# 3V3_Supply.net
KiCad netlist of a schematic drawn in Altium Designer
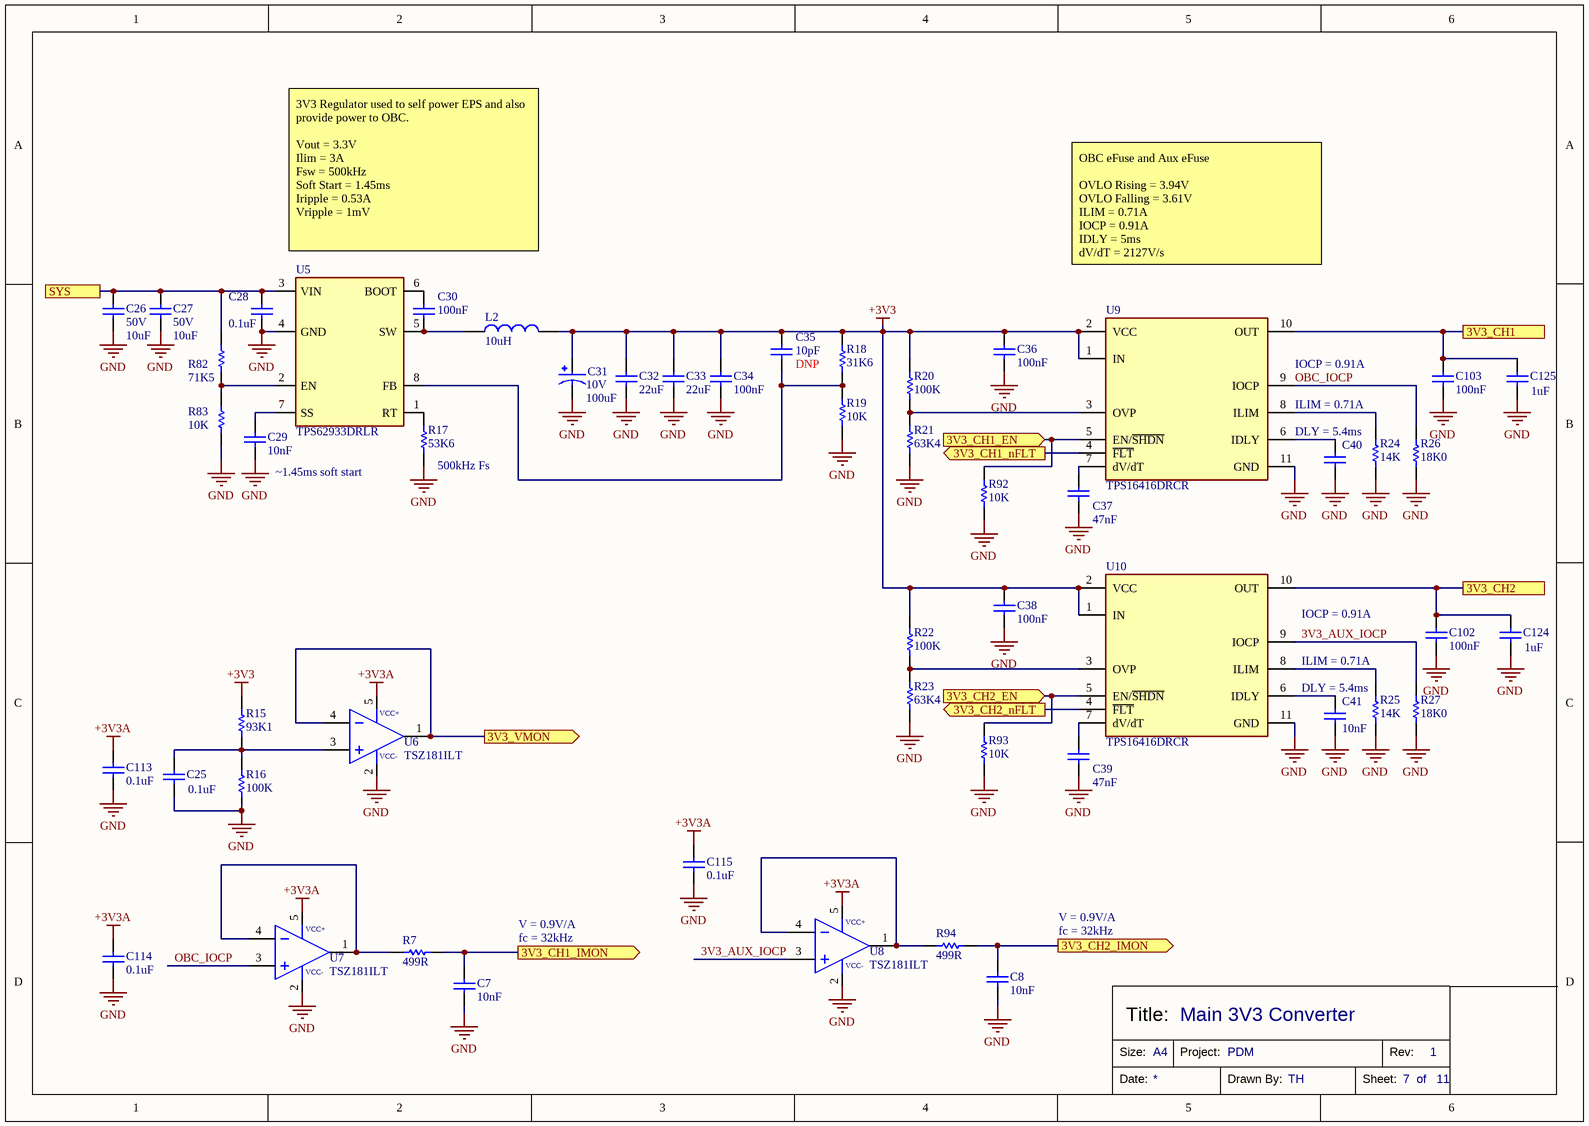
[diagram p0: 3V3_Supply.SchDoc]

(export (version "E")
  (design (tool "Eeschema 10.0.6"))
  (components
    (comp (ref "C7")
      (value "CL21B103KBANNNC")
      (footprint "CAPC0805X060")
      (description "10nF ±10% 50V Ceramic Capacitor X7R 0805 (2012 Metric)")
      (fields
        (field (name "DISTRIBUTOR PART NUMBER") "1276-1015-1-ND")
        (field (name "TOLERANCE") "10%")
        (field (name "CAPACITANCE") "10nF")
      )
      (libsource (lib "Ahristi_Library") (part "CL21B103KBANNNC"))
    )
    (comp (ref "C8")
      (value "CL21B103KBANNNC")
      (footprint "CAPC0805X060")
      (description "10nF ±10% 50V Ceramic Capacitor X7R 0805 (2012 Metric)")
      (fields
        (field (name "DISTRIBUTOR PART NUMBER") "1276-1015-1-ND")
        (field (name "TOLERANCE") "10%")
        (field (name "CAPACITANCE") "10nF")
      )
      (libsource (lib "Ahristi_Library") (part "CL21B103KBANNNC"))
    )
    (comp (ref "C25")
      (value "CL21B104KACNNNC")
      (footprint "CAPC0805X060")
      (description "0.1uF ±10% 25V Ceramic Capacitor X7R 0805 (2012 Metric)")
      (fields
        (field (name "DISTRIBUTOR PART NUMBER") "1276-1099-1-ND")
        (field (name "TOLERANCE") "10%")
        (field (name "CAPACITANCE") "0.1uF")
      )
      (libsource (lib "Ahristi_Library") (part "CL21B104KACNNNC"))
    )
    (comp (ref "C26")
      (value "CL32B106KBJNNNE")
      (footprint "CAPC1210X090")
      (description "10 µF ±10% 50V Ceramic Capacitor X7R 1210 (3225 Metric)")
      (fields
        (field (name "DISTRIBUTOR PART NUMBER") "1276-3387-1-ND")
        (field (name "TOLERANCE") "10%")
        (field (name "VOLTAGE RATING") "50V")
        (field (name "CAPACITANCE") "10uF")
      )
      (libsource (lib "Ahristi_Library") (part "CL32B106KBJNNNE"))
    )
    (comp (ref "C27")
      (value "CL32B106KBJNNNE")
      (footprint "CAPC1210X090")
      (description "10 µF ±10% 50V Ceramic Capacitor X7R 1210 (3225 Metric)")
      (fields
        (field (name "DISTRIBUTOR PART NUMBER") "1276-3387-1-ND")
        (field (name "TOLERANCE") "10%")
        (field (name "VOLTAGE RATING") "50V")
        (field (name "CAPACITANCE") "10uF")
      )
      (libsource (lib "Ahristi_Library") (part "CL32B106KBJNNNE"))
    )
    (comp (ref "C28")
      (value "CL05B104KB5NNNC")
      (footprint "CAPC0402X020")
      (description "0.1 µF ±10% 50V Ceramic Capacitor X7R 0402 (1005 Metric)")
      (fields
        (field (name "TOLERANCE") "10%")
        (field (name "DISTRIBUTOR PART NUMBER") "1276-CL05B104KB5NNNCCT-ND")
        (field (name "CAPACITANCE") "0.1uF")
      )
      (libsource (lib "Ahristi_Library") (part "CL05B104KB5NNNC"))
    )
    (comp (ref "C29")
      (value "CL21B103KBANNNC")
      (footprint "CAPC0805X060")
      (description "10nF ±10% 50V Ceramic Capacitor X7R 0805 (2012 Metric)")
      (fields
        (field (name "DISTRIBUTOR PART NUMBER") "1276-1015-1-ND")
        (field (name "TOLERANCE") "10%")
        (field (name "CAPACITANCE") "10nF")
      )
      (libsource (lib "Ahristi_Library") (part "CL21B103KBANNNC"))
    )
    (comp (ref "C30")
      (value "C0603C104K5RACTU")
      (footprint "CAPC0603X040")
      (description "0.1 µF ±10% 50V Ceramic Capacitor X7R 0603 (1608 Metric)")
      (fields
        (field (name "DISTRIBUTOR PART NUMBER") "399-C0603C104K5RACTUCT-ND")
        (field (name "TOLERANCE") "10%")
        (field (name "CAPACITANCE") "100nF")
      )
      (libsource (lib "Ahristi_Library") (part "C0603C104K5RACTU"))
    )
    (comp (ref "C31")
      (value "TPSC107K010R0100")
      (footprint "2312 Tantalum")
      (description "100 µF Molded Tantalum Capacitors 10 V 2312 (6032 Metric) 100mOhm")
      (fields
        (field (name "DISTRIBUTOR PART NUMBER") "478-1765-1-ND")
        (field (name "VOLTAGE RATING") "10V")
        (field (name "CAPACITANCE") "100uF")
      )
      (libsource (lib "Ahristi_Library") (part "TPSC107K010R0100"))
    )
    (comp (ref "C32")
      (value "GRM21BZ71A226ME15L")
      (footprint "CAPC0805X060")
      (description "22 µF ±20% 10V Ceramic Capacitor X7R 0805 (2012 Metric)")
      (fields
        (field (name "DISTRIBUTOR PART NUMBER") "490-GRM21BZ71A226ME15LCT-ND")
        (field (name "TOLERANCE") "10%")
        (field (name "CAPACITANCE") "22uF")
      )
      (libsource (lib "Ahristi_Library") (part "GRM21BZ71A226ME15L"))
    )
    (comp (ref "C33")
      (value "GRM21BZ71A226ME15L")
      (footprint "CAPC0805X060")
      (description "22 µF ±20% 10V Ceramic Capacitor X7R 0805 (2012 Metric)")
      (fields
        (field (name "DISTRIBUTOR PART NUMBER") "490-GRM21BZ71A226ME15LCT-ND")
        (field (name "TOLERANCE") "10%")
        (field (name "CAPACITANCE") "22uF")
      )
      (libsource (lib "Ahristi_Library") (part "GRM21BZ71A226ME15L"))
    )
    (comp (ref "C34")
      (value "C0603C104K5RACTU")
      (footprint "CAPC0603X040")
      (description "0.1 µF ±10% 50V Ceramic Capacitor X7R 0603 (1608 Metric)")
      (fields
        (field (name "DISTRIBUTOR PART NUMBER") "399-C0603C104K5RACTUCT-ND")
        (field (name "TOLERANCE") "10%")
        (field (name "CAPACITANCE") "100nF")
      )
      (libsource (lib "Ahristi_Library") (part "C0603C104K5RACTU"))
    )
    (comp (ref "C35")
      (value "C0603C104K5RACTU")
      (footprint "CAPC0603X040")
      (description "10 pF ±5% 50V Ceramic Capacitor C0G, NP0 0603 (1608 Metric)")
      (fields
        (field (name "PART NUMBER") "C0603C100J5GACTU")
        (field (name "DISTRIBUTOR PART NUMBER") "399-C0603C100J5GACTUCT-ND")
        (field (name "CAPACITANCE") "10pF")
      )
      (libsource (lib "Ahristi_Library") (part "C0603C100J5GACTU"))
    )
    (comp (ref "C36")
      (value "C0603C104K5RACTU")
      (footprint "CAPC0603X040")
      (description "0.1 µF ±10% 50V Ceramic Capacitor X7R 0603 (1608 Metric)")
      (fields
        (field (name "DISTRIBUTOR PART NUMBER") "399-C0603C104K5RACTUCT-ND")
        (field (name "TOLERANCE") "10%")
        (field (name "CAPACITANCE") "100nF")
      )
      (libsource (lib "Ahristi_Library") (part "C0603C104K5RACTU"))
    )
    (comp (ref "C37")
      (value "CL21B473KBCNNNC")
      (footprint "CAPC0805X060")
      (description "0.047 µF ±10% 50V Ceramic Capacitor X7R 0805 (2012 Metric)")
      (fields
        (field (name "DISTRIBUTOR PART NUMBER") "1276-1250-1-ND")
        (field (name "TOLERANCE") "10%")
        (field (name "CAPACITANCE") "47nF")
      )
      (libsource (lib "Ahristi_Library") (part "CL21B473KBCNNNC"))
    )
    (comp (ref "C38")
      (value "C0603C104K5RACTU")
      (footprint "CAPC0603X040")
      (description "0.1 µF ±10% 50V Ceramic Capacitor X7R 0603 (1608 Metric)")
      (fields
        (field (name "DISTRIBUTOR PART NUMBER") "399-C0603C104K5RACTUCT-ND")
        (field (name "TOLERANCE") "10%")
        (field (name "CAPACITANCE") "100nF")
      )
      (libsource (lib "Ahristi_Library") (part "C0603C104K5RACTU"))
    )
    (comp (ref "C39")
      (value "CL21B473KBCNNNC")
      (footprint "CAPC0805X060")
      (description "0.047 µF ±10% 50V Ceramic Capacitor X7R 0805 (2012 Metric)")
      (fields
        (field (name "DISTRIBUTOR PART NUMBER") "1276-1250-1-ND")
        (field (name "TOLERANCE") "10%")
        (field (name "CAPACITANCE") "47nF")
      )
      (libsource (lib "Ahristi_Library") (part "CL21B473KBCNNNC"))
    )
    (comp (ref "C40")
      (value "CL21B103KBANNNC")
      (footprint "CAPC0805X060")
      (description "10nF ±10% 50V Ceramic Capacitor X7R 0805 (2012 Metric)")
      (fields (field (name "DISTRIBUTOR PART NUMBER") "1276-1015-1-ND") (field (name "TOLERANCE") "10%"))
      (libsource (lib "Ahristi_Library") (part "CL21B103KBANNNC"))
    )
    (comp (ref "C41")
      (value "CL21B103KBANNNC")
      (footprint "CAPC0805X060")
      (description "10nF ±10% 50V Ceramic Capacitor X7R 0805 (2012 Metric)")
      (fields
        (field (name "DISTRIBUTOR PART NUMBER") "1276-1015-1-ND")
        (field (name "TOLERANCE") "10%")
        (field (name "CAPACITANCE") "10nF")
      )
      (libsource (lib "Ahristi_Library") (part "CL21B103KBANNNC"))
    )
    (comp (ref "C102")
      (value "C0603C104K5RACTU")
      (footprint "CAPC0603X040")
      (description "0.1 µF ±10% 50V Ceramic Capacitor X7R 0603 (1608 Metric)")
      (fields
        (field (name "DISTRIBUTOR PART NUMBER") "399-C0603C104K5RACTUCT-ND")
        (field (name "TOLERANCE") "10%")
        (field (name "CAPACITANCE") "100nF")
      )
      (libsource (lib "Ahristi_Library") (part "C0603C104K5RACTU"))
    )
    (comp (ref "C103")
      (value "C0603C104K5RACTU")
      (footprint "CAPC0603X040")
      (description "0.1 µF ±10% 50V Ceramic Capacitor X7R 0603 (1608 Metric)")
      (fields
        (field (name "DISTRIBUTOR PART NUMBER") "399-C0603C104K5RACTUCT-ND")
        (field (name "TOLERANCE") "10%")
        (field (name "CAPACITANCE") "100nF")
      )
      (libsource (lib "Ahristi_Library") (part "C0603C104K5RACTU"))
    )
    (comp (ref "C113")
      (value "C0603C104K5RACTU")
      (footprint "CAPC0603X040")
      (description "0.1 µF ±10% 50V Ceramic Capacitor X7R 0603 (1608 Metric)")
      (fields
        (field (name "DISTRIBUTOR PART NUMBER") "399-C0603C104K5RACTUCT-ND")
        (field (name "TOLERANCE") "10%")
        (field (name "CAPACITANCE") "0.1uF")
      )
      (libsource (lib "Ahristi_Library") (part "C0603C104K5RACTU"))
    )
    (comp (ref "C114")
      (value "C0603C104K5RACTU")
      (footprint "CAPC0603X040")
      (description "0.1 µF ±10% 50V Ceramic Capacitor X7R 0603 (1608 Metric)")
      (fields
        (field (name "DISTRIBUTOR PART NUMBER") "399-C0603C104K5RACTUCT-ND")
        (field (name "TOLERANCE") "10%")
        (field (name "CAPACITANCE") "0.1uF")
      )
      (libsource (lib "Ahristi_Library") (part "C0603C104K5RACTU"))
    )
    (comp (ref "C115")
      (value "C0603C104K5RACTU")
      (footprint "CAPC0603X040")
      (description "0.1 µF ±10% 50V Ceramic Capacitor X7R 0603 (1608 Metric)")
      (fields
        (field (name "DISTRIBUTOR PART NUMBER") "399-C0603C104K5RACTUCT-ND")
        (field (name "TOLERANCE") "10%")
        (field (name "CAPACITANCE") "0.1uF")
      )
      (libsource (lib "Ahristi_Library") (part "C0603C104K5RACTU"))
    )
    (comp (ref "C124")
      (value "CL21B105KAFNNNE")
      (footprint "CAPC0805X060")
      (description "1uF ±10% 25V Ceramic Capacitor X7R 0805 (2012 Metric)")
      (fields
        (field (name "DISTRIBUTOR PART NUMBER") "1276-1066-1-ND")
        (field (name "TOLERANCE") "10%")
        (field (name "CAPACITANCE") "1uF")
      )
      (libsource (lib "Ahristi_Library") (part "CL21B105KAFNNNE"))
    )
    (comp (ref "C125")
      (value "CL21B105KAFNNNE")
      (footprint "CAPC0805X060")
      (description "1uF ±10% 25V Ceramic Capacitor X7R 0805 (2012 Metric)")
      (fields
        (field (name "DISTRIBUTOR PART NUMBER") "1276-1066-1-ND")
        (field (name "TOLERANCE") "10%")
        (field (name "CAPACITANCE") "1uF")
      )
      (libsource (lib "Ahristi_Library") (part "CL21B105KAFNNNE"))
    )
    (comp (ref "L2")
      (value "1274AS-H-100M=P3")
      (footprint "1274AS-H-100M=P3")
      (description "Inductor 10 µH , 4.4 A 30.4mOhm Max Shielded Drum Core")
      (fields (field (name "DISTRIBUTOR PART NUMBER") "490-10846-1-ND") (field (name "INDUCTANCE") "10uH"))
      (libsource (lib "Ahristi_Library") (part "1274AS-H-100M=P3"))
    )
    (comp (ref "R7")
      (value "RMCF0805FT499R")
      (footprint "RESC0805")
      (description "499 Ohms ±1% 0.125W, 1/8W Chip Resistor 0805 (2012 Metric) Automotive AEC-Q200 Thick Film")
      (fields
        (field (name "TOLERANCE") "1%")
        (field (name "DISTRIBUTOR PART NUMBER") "RMCF0805FT499RCT-ND")
        (field (name "RESISTANCE") "499R")
      )
      (libsource (lib "Ahristi_Library") (part "RMCF0805FT499R"))
    )
    (comp (ref "R15")
      (value "RMCF0603FT93K1")
      (footprint "RESC0603")
      (description "93.1 kOhms ±1% 0.1W, 1/10W Chip Resistor 0603 (1608 Metric) Automotive AEC-Q200 Thick Film")
      (fields
        (field (name "TOLERANCE") "1%")
        (field (name "DISTRIBUTOR PART NUMBER") "RMCF0603FT93K1CT-ND")
        (field (name "RESISTANCE") "93K1")
      )
      (libsource (lib "Ahristi_Library") (part "RMCF0603FT93K1"))
    )
    (comp (ref "R16")
      (value "RMCF0603FT100K")
      (footprint "RESC0603")
      (description "100 kOhms ±1% 0.1W, 1/10W Chip Resistor 0603 (1608 Metric) Automotive AEC-Q200 Thick Film")
      (fields
        (field (name "TOLERANCE") "1%")
        (field (name "DISTRIBUTOR PART NUMBER") "RMCF0603FT100KCT-ND")
        (field (name "RESISTANCE") "100K")
      )
      (libsource (lib "Ahristi_Library") (part "RMCF0603FT100K"))
    )
    (comp (ref "R17")
      (value "RMCF0805FT53K6")
      (footprint "RESC0805")
      (description "53.6 kOhms ±1% 0.125W, 1/8W Chip Resistor 0805 (2012 Metric) Automotive AEC-Q200 Thick Film")
      (fields
        (field (name "TOLERANCE") "1%")
        (field (name "DISTRIBUTOR PART NUMBER") "RMCF0805FT53K6CT-ND")
        (field (name "RESISTANCE") "53K6")
      )
      (libsource (lib "Ahristi_Library") (part "RMCF0805FT53K6"))
    )
    (comp (ref "R18")
      (value "RMCF0603FT31K6")
      (footprint "RESC0603")
      (description "31.6 kOhms ±1% 0.1W, 1/10W Chip Resistor 0603 (1608 Metric) Automotive AEC-Q200 Thick Film")
      (fields
        (field (name "TOLERANCE") "1%")
        (field (name "DISTRIBUTOR PART NUMBER") "RMCF0603FT31K6CT-ND")
        (field (name "RESISTANCE") "31K6")
      )
      (libsource (lib "Ahristi_Library") (part "RMCF0603FT31K6"))
    )
    (comp (ref "R19")
      (value "RMCF0603FT10K0")
      (footprint "RESC0603")
      (description "10 kOhms ±1% 0.1W, 1/10W Chip Resistor 0603 (1608 Metric) Automotive AEC-Q200 Thick Film")
      (fields
        (field (name "TOLERANCE") "1%")
        (field (name "DISTRIBUTOR PART NUMBER") "RMCF0603FT10K0CT-ND")
        (field (name "RESISTANCE") "10K")
      )
      (libsource (lib "Ahristi_Library") (part "RMCF0603FT10K0"))
    )
    (comp (ref "R20")
      (value "RMCF0805FG100K")
      (footprint "RESC0805")
      (description "100 kOhms ±1% 0.125W, 1/8W Chip Resistor 0805 (2012 Metric) Automotive AEC-Q200 Thick Film")
      (fields
        (field (name "TOLERANCE") "1%")
        (field (name "DISTRIBUTOR PART NUMBER") "RMCF0805FG100KCT-ND")
        (field (name "RESISTANCE") "100K")
      )
      (libsource (lib "Ahristi_Library") (part "RMCF0805FG100K"))
    )
    (comp (ref "R21")
      (value "RMCF0805FT63K4")
      (footprint "RESC0805")
      (description "63.4 kOhms ±1% 0.125W, 1/8W Chip Resistor 0805 (2012 Metric) Automotive AEC-Q200 Thick Film")
      (fields
        (field (name "TOLERANCE") "1%")
        (field (name "DISTRIBUTOR PART NUMBER") "RMCF0805FT63K4CT-ND")
        (field (name "RESISTANCE") "63K4")
      )
      (libsource (lib "Ahristi_Library") (part "RMCF0805FT63K4"))
    )
    (comp (ref "R22")
      (value "RMCF0805FG100K")
      (footprint "RESC0805")
      (description "100 kOhms ±1% 0.125W, 1/8W Chip Resistor 0805 (2012 Metric) Automotive AEC-Q200 Thick Film")
      (fields
        (field (name "TOLERANCE") "1%")
        (field (name "DISTRIBUTOR PART NUMBER") "RMCF0805FG100KCT-ND")
        (field (name "RESISTANCE") "100K")
      )
      (libsource (lib "Ahristi_Library") (part "RMCF0805FG100K"))
    )
    (comp (ref "R23")
      (value "RMCF0805FT63K4")
      (footprint "RESC0805")
      (description "63.4 kOhms ±1% 0.125W, 1/8W Chip Resistor 0805 (2012 Metric) Automotive AEC-Q200 Thick Film")
      (fields
        (field (name "TOLERANCE") "1%")
        (field (name "DISTRIBUTOR PART NUMBER") "RMCF0805FT63K4CT-ND")
        (field (name "RESISTANCE") "63K4")
      )
      (libsource (lib "Ahristi_Library") (part "RMCF0805FT63K4"))
    )
    (comp (ref "R24")
      (value "RMCF0805FT14K0")
      (footprint "RESC0805")
      (description "14 kOhms ±1% 0.125W, 1/8W Chip Resistor 0805 (2012 Metric) Automotive AEC-Q200 Thick Film")
      (fields
        (field (name "TOLERANCE") "1%")
        (field (name "DISTRIBUTOR PART NUMBER") "RMCF0805FT14K0CT-ND")
        (field (name "RESISTANCE") "14K")
      )
      (libsource (lib "Ahristi_Library") (part "RMCF0805FT14K0"))
    )
    (comp (ref "R25")
      (value "RMCF0805FT14K0")
      (footprint "RESC0805")
      (description "14 kOhms ±1% 0.125W, 1/8W Chip Resistor 0805 (2012 Metric) Automotive AEC-Q200 Thick Film")
      (fields
        (field (name "TOLERANCE") "1%")
        (field (name "DISTRIBUTOR PART NUMBER") "RMCF0805FT14K0CT-ND")
        (field (name "RESISTANCE") "14K")
      )
      (libsource (lib "Ahristi_Library") (part "RMCF0805FT14K0"))
    )
    (comp (ref "R26")
      (value "RMCF0805FT18K0")
      (footprint "RESC0805")
      (description "18 kOhms ±1% 0.125W, 1/8W Chip Resistor 0805 (2012 Metric) Automotive AEC-Q200 Thick Film")
      (fields
        (field (name "TOLERANCE") "1%")
        (field (name "DISTRIBUTOR PART NUMBER") "RMCF0805FT18K0CT-ND")
        (field (name "RESISTANCE") "18K0")
      )
      (libsource (lib "Ahristi_Library") (part "RMCF0805FT18K0"))
    )
    (comp (ref "R27")
      (value "RMCF0805FT18K0")
      (footprint "RESC0805")
      (description "18 kOhms ±1% 0.125W, 1/8W Chip Resistor 0805 (2012 Metric) Automotive AEC-Q200 Thick Film")
      (fields
        (field (name "TOLERANCE") "1%")
        (field (name "DISTRIBUTOR PART NUMBER") "RMCF0805FT18K0CT-ND")
        (field (name "RESISTANCE") "18K0")
      )
      (libsource (lib "Ahristi_Library") (part "RMCF0805FT18K0"))
    )
    (comp (ref "R82")
      (value "RMCF0805FT71K5")
      (footprint "RESC0805")
      (description "71.5 kOhms ±1% 0.125W, 1/8W Chip Resistor 0805 (2012 Metric) Automotive AEC-Q200 Thick Film")
      (fields
        (field (name "TOLERANCE") "1%")
        (field (name "DISTRIBUTOR PART NUMBER") "RMCF0805FT71K5CT-ND")
        (field (name "RESISTANCE") "71K5")
      )
      (libsource (lib "Ahristi_Library") (part "RMCF0805FT71K5"))
    )
    (comp (ref "R83")
      (value "RMCF0603FT10K0")
      (footprint "RESC0603")
      (description "10 kOhms ±1% 0.1W, 1/10W Chip Resistor 0603 (1608 Metric) Automotive AEC-Q200 Thick Film")
      (fields
        (field (name "TOLERANCE") "1%")
        (field (name "DISTRIBUTOR PART NUMBER") "RMCF0603FT10K0CT-ND")
        (field (name "RESISTANCE") "10K")
      )
      (libsource (lib "Ahristi_Library") (part "RMCF0603FT10K0"))
    )
    (comp (ref "R92")
      (value "RMCF0805FT10K0")
      (footprint "RESC0805")
      (description "10 kOhms ±1% 0.125W, 1/8W Chip Resistor 0805 (2012 Metric) Automotive AEC-Q200 Thick Film")
      (fields
        (field (name "TOLERANCE") "1%")
        (field (name "DISTRIBUTOR PART NUMBER") "RMCF0805FT10K0CT-ND")
        (field (name "RESISTANCE") "10K")
      )
      (libsource (lib "Ahristi_Library") (part "RMCF0805FT10K0"))
    )
    (comp (ref "R93")
      (value "RMCF0805FT10K0")
      (footprint "RESC0805")
      (description "10 kOhms ±1% 0.125W, 1/8W Chip Resistor 0805 (2012 Metric) Automotive AEC-Q200 Thick Film")
      (fields
        (field (name "TOLERANCE") "1%")
        (field (name "DISTRIBUTOR PART NUMBER") "RMCF0805FT10K0CT-ND")
        (field (name "RESISTANCE") "10K")
      )
      (libsource (lib "Ahristi_Library") (part "RMCF0805FT10K0"))
    )
    (comp (ref "R94")
      (value "RMCF0805FT499R")
      (footprint "RESC0805")
      (description "499 Ohms ±1% 0.125W, 1/8W Chip Resistor 0805 (2012 Metric) Automotive AEC-Q200 Thick Film")
      (fields
        (field (name "TOLERANCE") "1%")
        (field (name "DISTRIBUTOR PART NUMBER") "RMCF0805FT499RCT-ND")
        (field (name "RESISTANCE") "499R")
      )
      (libsource (lib "Ahristi_Library") (part "RMCF0805FT499R"))
    )
    (comp (ref "U5")
      (value "TPS62933DRLR")
      (footprint "SOT-583")
      (description "Buck Switching Regulator IC Positive Adjustable 0.8V 1 Output 3A SOT-583")
      (fields (field (name "DISTRIBUTOR PART NUMBER") "296-TPS62933DRLRCT-ND"))
      (libsource (lib "Ahristi_Library") (part "TPS62933DRLR"))
    )
    (comp (ref "U6")
      (value "TSZ181ILT")
      (footprint "SOT23-5 IC")
      (description "Operational Amplifier, General Purpose, 2.2V~5.5V")
      (fields (field (name "DISTRIBUTOR PART NUMBER") "497-18084-1-ND"))
      (libsource (lib "Ahristi_Library") (part "TSZ181ILT"))
    )
    (comp (ref "U7")
      (value "TSZ181ILT")
      (footprint "SOT23-5 IC")
      (description "Operational Amplifier, General Purpose, 2.2V~5.5V")
      (fields (field (name "DISTRIBUTOR PART NUMBER") "497-18084-1-ND"))
      (libsource (lib "Ahristi_Library") (part "TSZ181ILT"))
    )
    (comp (ref "U8")
      (value "TSZ181ILT")
      (footprint "SOT23-5 IC")
      (description "Operational Amplifier, General Purpose, 2.2V~5.5V")
      (fields (field (name "DISTRIBUTOR PART NUMBER") "497-18084-1-ND"))
      (libsource (lib "Ahristi_Library") (part "TSZ181ILT"))
    )
    (comp (ref "U9")
      (value "TPS16410DRCR")
      (footprint "TPS1641")
      (description "2.7-V to 40-V 152-mΩ 1.8-A eFuse with output power limiting")
      (fields
        (field (name "DISTRIBUTOR PART NUMBER") "296-TPS16410DRCRCT-ND")
        (field (name "PART NUMBER") "TPS16416DRCR")
      )
      (libsource (lib "Ahristi_Library") (part "TPS16410DRCR"))
    )
    (comp (ref "U10")
      (value "TPS16410DRCR")
      (footprint "TPS1641")
      (description "2.7-V to 40-V 152-mΩ 1.8-A eFuse with output power limiting")
      (fields
        (field (name "DISTRIBUTOR PART NUMBER") "296-TPS16410DRCRCT-ND")
        (field (name "PART NUMBER") "TPS16416DRCR")
      )
      (libsource (lib "Ahristi_Library") (part "TPS16410DRCR"))
    )
  )
  (nets
    (net (code "1") (name "+3V3") (class "Default")
      (node (ref "C31") (pin "1") (pinfunction "1_1") (pintype "passive"))
      (node (ref "C32") (pin "2") (pinfunction "2_2") (pintype "passive"))
      (node (ref "C33") (pin "2") (pinfunction "2_2") (pintype "passive"))
      (node (ref "C34") (pin "2") (pinfunction "2_2") (pintype "passive"))
      (node (ref "C35") (pin "2") (pinfunction "2_2") (pintype "passive"))
      (node (ref "C36") (pin "2") (pinfunction "2_2") (pintype "passive"))
      (node (ref "C38") (pin "2") (pinfunction "2_2") (pintype "passive"))
      (node (ref "L2") (pin "2") (pinfunction "2_2") (pintype "passive"))
      (node (ref "R15") (pin "2") (pinfunction "2_2") (pintype "passive"))
      (node (ref "R18") (pin "2") (pinfunction "2_2") (pintype "passive"))
      (node (ref "R20") (pin "2") (pinfunction "2_2") (pintype "passive"))
      (node (ref "R22") (pin "2") (pinfunction "2_2") (pintype "passive"))
      (node (ref "U10") (pin "1") (pinfunction "IN_1") (pintype "passive"))
      (node (ref "U10") (pin "2") (pinfunction "VCC_2") (pintype "passive"))
      (node (ref "U9") (pin "1") (pinfunction "IN_1") (pintype "passive"))
      (node (ref "U9") (pin "2") (pinfunction "VCC_2") (pintype "passive"))
    )
    (net (code "2") (name "+3V3A") (class "Default")
      (node (ref "C113") (pin "2") (pinfunction "2_2") (pintype "passive"))
      (node (ref "C114") (pin "2") (pinfunction "2_2") (pintype "passive"))
      (node (ref "C115") (pin "2") (pinfunction "2_2") (pintype "passive"))
      (node (ref "U6") (pin "5") (pinfunction "VCC+_5") (pintype "power_in"))
      (node (ref "U7") (pin "5") (pinfunction "VCC+_5") (pintype "power_in"))
      (node (ref "U8") (pin "5") (pinfunction "VCC+_5") (pintype "power_in"))
    )
    (net (code "3") (name "/3V3_AUX_IOCP") (class "Default")
      (node (ref "R27") (pin "2") (pinfunction "2_2") (pintype "passive"))
      (node (ref "U10") (pin "9") (pinfunction "IOCP_9") (pintype "passive"))
      (node (ref "U8") (pin "3") (pinfunction "IN+_3") (pintype "passive"))
    )
    (net (code "4") (name "/3V3_CH1") (class "Default")
      (node (ref "C103") (pin "2") (pinfunction "2_2") (pintype "passive"))
      (node (ref "C125") (pin "2") (pinfunction "2_2") (pintype "passive"))
      (node (ref "U9") (pin "10") (pinfunction "OUT_10") (pintype "passive"))
    )
    (net (code "5") (name "/3V3_CH1_EN") (class "Default")
      (node (ref "R92") (pin "2") (pinfunction "2_2") (pintype "passive"))
      (node (ref "U9") (pin "5") (pinfunction "EN/~{SHDN}_5") (pintype "passive"))
    )
    (net (code "6") (name "/3V3_CH1_IMON") (class "Default")
      (node (ref "C7") (pin "2") (pinfunction "2_2") (pintype "passive"))
      (node (ref "R7") (pin "2") (pinfunction "2_2") (pintype "passive"))
    )
    (net (code "7") (name "/3V3_CH1_nFLT") (class "Default")
      (node (ref "U9") (pin "4") (pinfunction "~{FLT}_4") (pintype "passive"))
    )
    (net (code "8") (name "/3V3_CH2") (class "Default")
      (node (ref "C102") (pin "2") (pinfunction "2_2") (pintype "passive"))
      (node (ref "C124") (pin "2") (pinfunction "2_2") (pintype "passive"))
      (node (ref "U10") (pin "10") (pinfunction "OUT_10") (pintype "passive"))
    )
    (net (code "9") (name "/3V3_CH2_EN") (class "Default")
      (node (ref "R93") (pin "2") (pinfunction "2_2") (pintype "passive"))
      (node (ref "U10") (pin "5") (pinfunction "EN/~{SHDN}_5") (pintype "passive"))
    )
    (net (code "10") (name "/3V3_CH2_IMON") (class "Default")
      (node (ref "C8") (pin "2") (pinfunction "2_2") (pintype "passive"))
      (node (ref "R94") (pin "2") (pinfunction "2_2") (pintype "passive"))
    )
    (net (code "11") (name "/3V3_CH2_nFLT") (class "Default")
      (node (ref "U10") (pin "4") (pinfunction "~{FLT}_4") (pintype "passive"))
    )
    (net (code "12") (name "/3V3_VMON") (class "Default")
      (node (ref "U6") (pin "1") (pinfunction "OUT_1") (pintype "passive"))
      (node (ref "U6") (pin "4") (pinfunction "IN-_4") (pintype "passive"))
    )
    (net (code "13") (name "/OBC_IOCP") (class "Default")
      (node (ref "R26") (pin "2") (pinfunction "2_2") (pintype "passive"))
      (node (ref "U7") (pin "3") (pinfunction "IN+_3") (pintype "passive"))
      (node (ref "U9") (pin "9") (pinfunction "IOCP_9") (pintype "passive"))
    )
    (net (code "14") (name "/SYS") (class "Default")
      (node (ref "C26") (pin "2") (pinfunction "2_2") (pintype "passive"))
      (node (ref "C27") (pin "2") (pinfunction "2_2") (pintype "passive"))
      (node (ref "C28") (pin "2") (pinfunction "2_2") (pintype "passive"))
      (node (ref "R82") (pin "2") (pinfunction "2_2") (pintype "passive"))
      (node (ref "U5") (pin "3") (pinfunction "VIN_3") (pintype "passive"))
    )
    (net (code "15") (name "GND") (class "Default")
      (node (ref "C102") (pin "1") (pinfunction "1_1") (pintype "passive"))
      (node (ref "C103") (pin "1") (pinfunction "1_1") (pintype "passive"))
      (node (ref "C113") (pin "1") (pinfunction "1_1") (pintype "passive"))
      (node (ref "C114") (pin "1") (pinfunction "1_1") (pintype "passive"))
      (node (ref "C115") (pin "1") (pinfunction "1_1") (pintype "passive"))
      (node (ref "C124") (pin "1") (pinfunction "1_1") (pintype "passive"))
      (node (ref "C125") (pin "1") (pinfunction "1_1") (pintype "passive"))
      (node (ref "C25") (pin "1") (pinfunction "1_1") (pintype "passive"))
      (node (ref "C26") (pin "1") (pinfunction "1_1") (pintype "passive"))
      (node (ref "C27") (pin "1") (pinfunction "1_1") (pintype "passive"))
      (node (ref "C28") (pin "1") (pinfunction "1_1") (pintype "passive"))
      (node (ref "C29") (pin "1") (pinfunction "1_1") (pintype "passive"))
      (node (ref "C31") (pin "2") (pinfunction "2_2") (pintype "passive"))
      (node (ref "C32") (pin "1") (pinfunction "1_1") (pintype "passive"))
      (node (ref "C33") (pin "1") (pinfunction "1_1") (pintype "passive"))
      (node (ref "C34") (pin "1") (pinfunction "1_1") (pintype "passive"))
      (node (ref "C36") (pin "1") (pinfunction "1_1") (pintype "passive"))
      (node (ref "C37") (pin "1") (pinfunction "1_1") (pintype "passive"))
      (node (ref "C38") (pin "1") (pinfunction "1_1") (pintype "passive"))
      (node (ref "C39") (pin "1") (pinfunction "1_1") (pintype "passive"))
      (node (ref "C40") (pin "1") (pinfunction "1_1") (pintype "passive"))
      (node (ref "C41") (pin "1") (pinfunction "1_1") (pintype "passive"))
      (node (ref "C7") (pin "1") (pinfunction "1_1") (pintype "passive"))
      (node (ref "C8") (pin "1") (pinfunction "1_1") (pintype "passive"))
      (node (ref "R16") (pin "1") (pinfunction "1_1") (pintype "passive"))
      (node (ref "R17") (pin "1") (pinfunction "1_1") (pintype "passive"))
      (node (ref "R19") (pin "1") (pinfunction "1_1") (pintype "passive"))
      (node (ref "R21") (pin "1") (pinfunction "1_1") (pintype "passive"))
      (node (ref "R23") (pin "1") (pinfunction "1_1") (pintype "passive"))
      (node (ref "R24") (pin "1") (pinfunction "1_1") (pintype "passive"))
      (node (ref "R25") (pin "1") (pinfunction "1_1") (pintype "passive"))
      (node (ref "R26") (pin "1") (pinfunction "1_1") (pintype "passive"))
      (node (ref "R27") (pin "1") (pinfunction "1_1") (pintype "passive"))
      (node (ref "R83") (pin "1") (pinfunction "1_1") (pintype "passive"))
      (node (ref "R92") (pin "1") (pinfunction "1_1") (pintype "passive"))
      (node (ref "R93") (pin "1") (pinfunction "1_1") (pintype "passive"))
      (node (ref "U10") (pin "11") (pinfunction "GND_11") (pintype "passive"))
      (node (ref "U5") (pin "4") (pinfunction "GND_4") (pintype "passive"))
      (node (ref "U6") (pin "2") (pinfunction "VCC-_2") (pintype "power_in"))
      (node (ref "U7") (pin "2") (pinfunction "VCC-_2") (pintype "power_in"))
      (node (ref "U8") (pin "2") (pinfunction "VCC-_2") (pintype "power_in"))
      (node (ref "U9") (pin "11") (pinfunction "GND_11") (pintype "passive"))
    )
    (net (code "16") (name "Net-(U5-BOOT)") (class "Default")
      (node (ref "C30") (pin "2") (pinfunction "2_2") (pintype "passive"))
      (node (ref "U5") (pin "6") (pinfunction "BOOT_6") (pintype "passive"))
    )
    (net (code "17") (name "Net-(U5-EN)") (class "Default")
      (node (ref "R82") (pin "1") (pinfunction "1_1") (pintype "passive"))
      (node (ref "R83") (pin "2") (pinfunction "2_2") (pintype "passive"))
      (node (ref "U5") (pin "2") (pinfunction "EN_2") (pintype "passive"))
    )
    (net (code "18") (name "Net-(U5-FB)") (class "Default")
      (node (ref "C35") (pin "1") (pinfunction "1_1") (pintype "passive"))
      (node (ref "R18") (pin "1") (pinfunction "1_1") (pintype "passive"))
      (node (ref "R19") (pin "2") (pinfunction "2_2") (pintype "passive"))
      (node (ref "U5") (pin "8") (pinfunction "FB_8") (pintype "passive"))
    )
    (net (code "19") (name "Net-(U5-RT)") (class "Default")
      (node (ref "R17") (pin "2") (pinfunction "2_2") (pintype "passive"))
      (node (ref "U5") (pin "1") (pinfunction "RT_1") (pintype "passive"))
    )
    (net (code "20") (name "Net-(U5-SS)") (class "Default")
      (node (ref "C29") (pin "2") (pinfunction "2_2") (pintype "passive"))
      (node (ref "U5") (pin "7") (pinfunction "SS_7") (pintype "passive"))
    )
    (net (code "21") (name "Net-(U5-SW)") (class "Default")
      (node (ref "C30") (pin "1") (pinfunction "1_1") (pintype "passive"))
      (node (ref "L2") (pin "1") (pinfunction "1_1") (pintype "passive"))
      (node (ref "U5") (pin "5") (pinfunction "SW_5") (pintype "passive"))
    )
    (net (code "22") (name "Net-(U6-IN+)") (class "Default")
      (node (ref "C25") (pin "2") (pinfunction "2_2") (pintype "passive"))
      (node (ref "R15") (pin "1") (pinfunction "1_1") (pintype "passive"))
      (node (ref "R16") (pin "2") (pinfunction "2_2") (pintype "passive"))
      (node (ref "U6") (pin "3") (pinfunction "IN+_3") (pintype "passive"))
    )
    (net (code "23") (name "Net-(U7-IN-)") (class "Default")
      (node (ref "R7") (pin "1") (pinfunction "1_1") (pintype "passive"))
      (node (ref "U7") (pin "1") (pinfunction "OUT_1") (pintype "passive"))
      (node (ref "U7") (pin "4") (pinfunction "IN-_4") (pintype "passive"))
    )
    (net (code "24") (name "Net-(U8-IN-)") (class "Default")
      (node (ref "R94") (pin "1") (pinfunction "1_1") (pintype "passive"))
      (node (ref "U8") (pin "1") (pinfunction "OUT_1") (pintype "passive"))
      (node (ref "U8") (pin "4") (pinfunction "IN-_4") (pintype "passive"))
    )
    (net (code "25") (name "Net-(U9-IDLY)") (class "Default")
      (node (ref "C40") (pin "2") (pinfunction "2_2") (pintype "passive"))
      (node (ref "U9") (pin "6") (pinfunction "IDLY_6") (pintype "passive"))
    )
    (net (code "26") (name "Net-(U9-ILIM)") (class "Default")
      (node (ref "R24") (pin "2") (pinfunction "2_2") (pintype "passive"))
      (node (ref "U9") (pin "8") (pinfunction "ILIM_8") (pintype "passive"))
    )
    (net (code "27") (name "Net-(U9-OVP)") (class "Default")
      (node (ref "R20") (pin "1") (pinfunction "1_1") (pintype "passive"))
      (node (ref "R21") (pin "2") (pinfunction "2_2") (pintype "passive"))
      (node (ref "U9") (pin "3") (pinfunction "OVP_3") (pintype "passive"))
    )
    (net (code "28") (name "Net-(U9-dV{slash}dT)") (class "Default")
      (node (ref "C37") (pin "2") (pinfunction "2_2") (pintype "passive"))
      (node (ref "U9") (pin "7") (pinfunction "dV/dT_7") (pintype "passive"))
    )
    (net (code "29") (name "Net-(U10-IDLY)") (class "Default")
      (node (ref "C41") (pin "2") (pinfunction "2_2") (pintype "passive"))
      (node (ref "U10") (pin "6") (pinfunction "IDLY_6") (pintype "passive"))
    )
    (net (code "30") (name "Net-(U10-ILIM)") (class "Default")
      (node (ref "R25") (pin "2") (pinfunction "2_2") (pintype "passive"))
      (node (ref "U10") (pin "8") (pinfunction "ILIM_8") (pintype "passive"))
    )
    (net (code "31") (name "Net-(U10-OVP)") (class "Default")
      (node (ref "R22") (pin "1") (pinfunction "1_1") (pintype "passive"))
      (node (ref "R23") (pin "2") (pinfunction "2_2") (pintype "passive"))
      (node (ref "U10") (pin "3") (pinfunction "OVP_3") (pintype "passive"))
    )
    (net (code "32") (name "Net-(U10-dV{slash}dT)") (class "Default")
      (node (ref "C39") (pin "2") (pinfunction "2_2") (pintype "passive"))
      (node (ref "U10") (pin "7") (pinfunction "dV/dT_7") (pintype "passive"))
    )
  )
)
